# Adafruit_1_54inch_240x240_rev_G.net
KiCad netlist of a schematic drawn in EAGLE
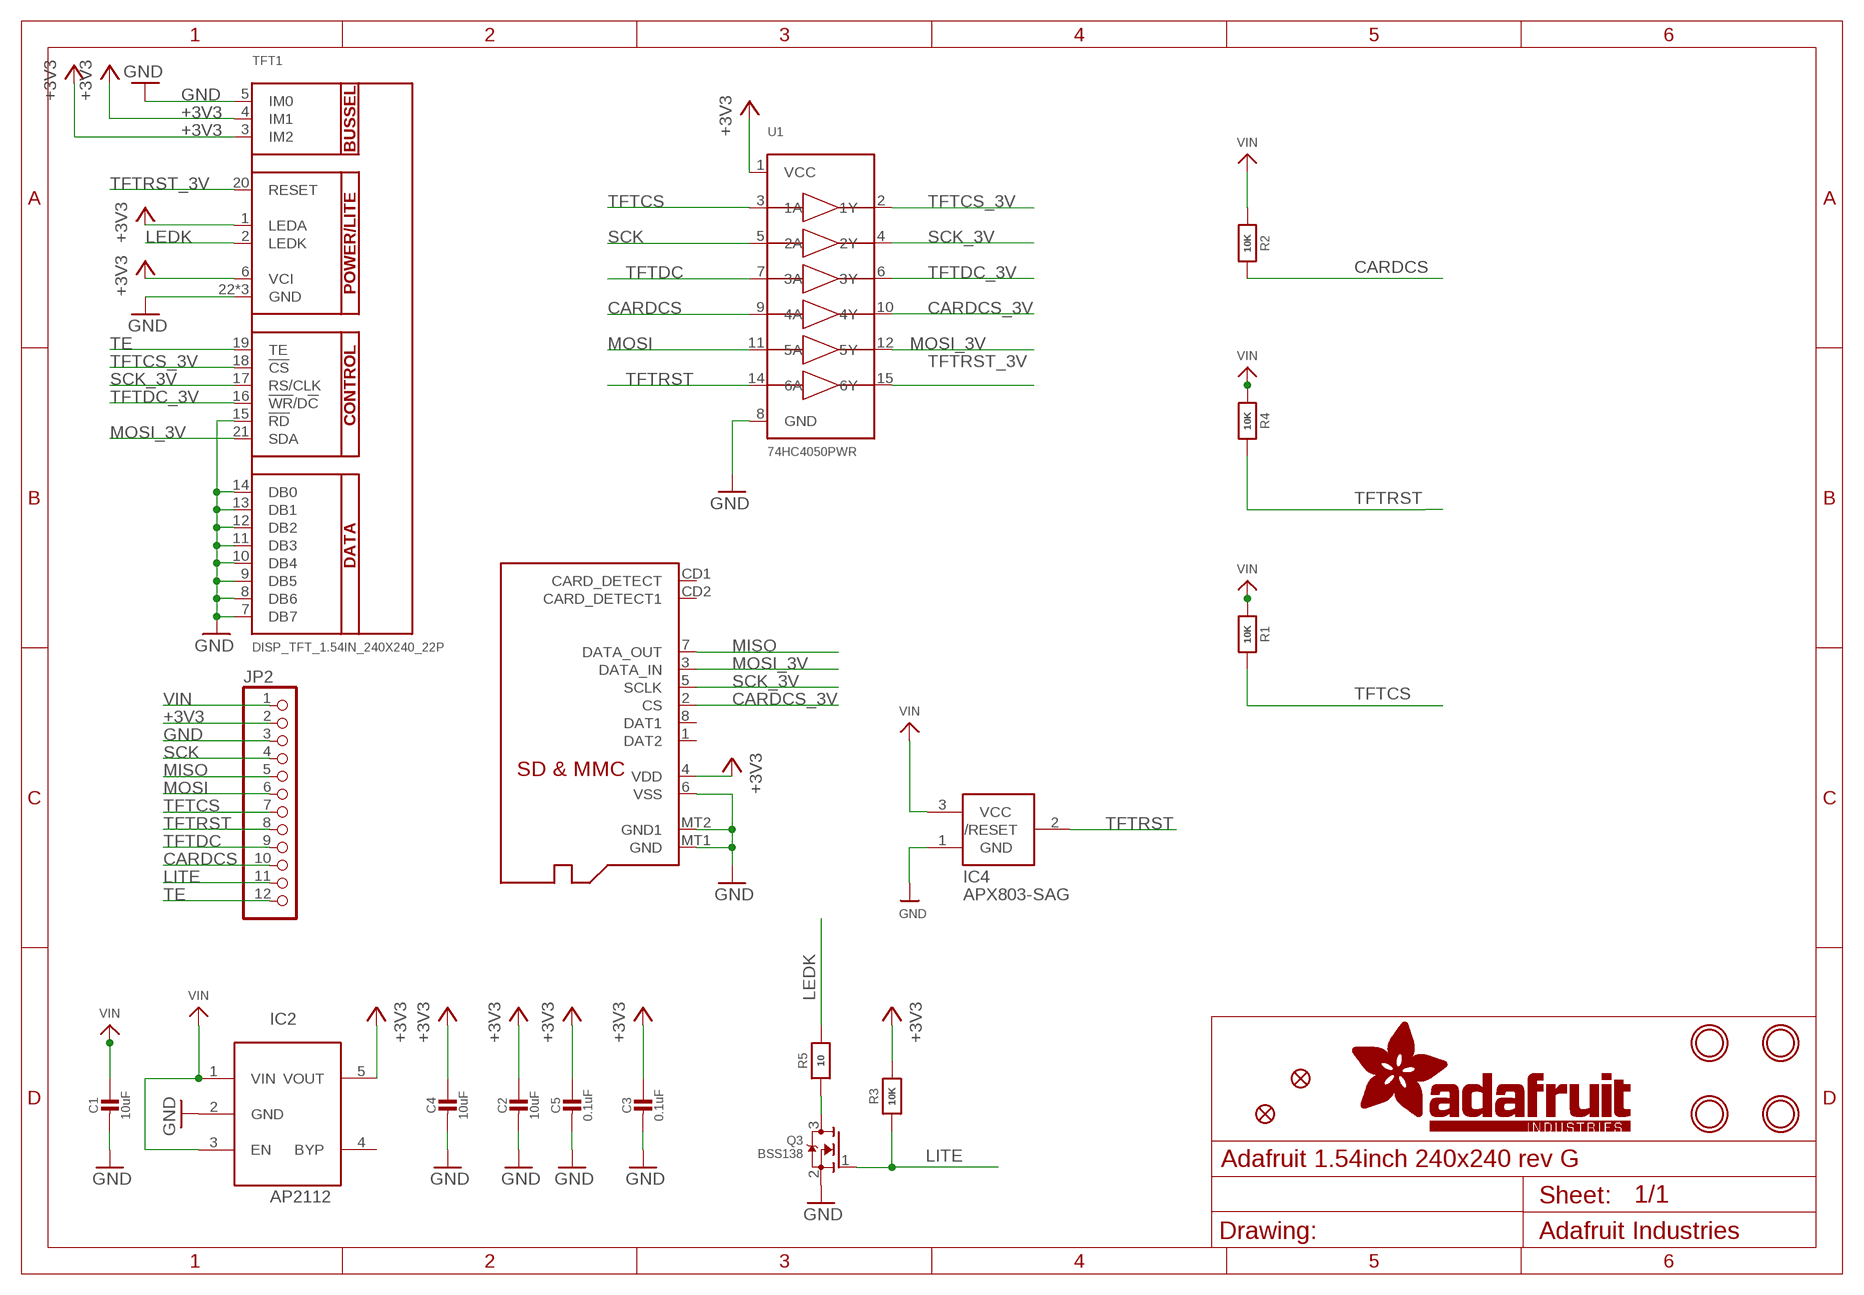
[diagram p0: schematic, sheet 1]

(export (version "E")
  (design (tool "Eeschema 10.0.6"))
  (components
    (comp (ref "C1")
      (value "10uF")
      (footprint "eagle-import:0805-NO")
      (libsource (lib "eagle-import") (part "CAP_CERAMIC0805-NOOUTLINE"))
    )
    (comp (ref "C2")
      (value "10uF")
      (footprint "eagle-import:0805-NO")
      (libsource (lib "eagle-import") (part "CAP_CERAMIC0805-NOOUTLINE"))
    )
    (comp (ref "C3")
      (value "0.1uF")
      (footprint "eagle-import:0603-NO")
      (libsource (lib "eagle-import") (part "CAP_CERAMIC0603_NO"))
    )
    (comp (ref "C4")
      (value "10uF")
      (footprint "eagle-import:0805-NO")
      (libsource (lib "eagle-import") (part "CAP_CERAMIC0805-NOOUTLINE"))
    )
    (comp (ref "C5")
      (value "0.1uF")
      (footprint "eagle-import:0603-NO")
      (libsource (lib "eagle-import") (part "CAP_CERAMIC0603_NO"))
    )
    (comp (ref "IC2")
      (value "AP2112")
      (footprint "eagle-import:SOT23-5L")
      (libsource (lib "eagle-import") (part "LP298XS"))
    )
    (comp (ref "IC4")
      (value "APX803-SAG")
      (footprint "eagle-import:SOT23")
      (libsource (lib "eagle-import") (part "AXP083-SAG"))
    )
    (comp (ref "JP2")
      (value "HEADER-1X1276MIL")
      (footprint "eagle-import:1X12_ROUND_76MIL")
      (libsource (lib "eagle-import") (part "HEADER-1X1276MIL"))
    )
    (comp (ref "Q2")
      (value "MICROSD")
      (footprint "eagle-import:MICROSD")
      (libsource (lib "eagle-import") (part "MICROSD"))
    )
    (comp (ref "Q3")
      (value "BSS138")
      (footprint "eagle-import:SOT23-WIDE")
      (libsource (lib "eagle-import") (part "MOSFET-NWIDE"))
    )
    (comp (ref "R1")
      (value "10K")
      (footprint "eagle-import:0603-NO")
      (libsource (lib "eagle-import") (part "RESISTOR_0603_NOOUT"))
    )
    (comp (ref "R2")
      (value "10K")
      (footprint "eagle-import:0603-NO")
      (libsource (lib "eagle-import") (part "RESISTOR_0603_NOOUT"))
    )
    (comp (ref "R3")
      (value "10K")
      (footprint "eagle-import:0603-NO")
      (libsource (lib "eagle-import") (part "RESISTOR_0603_NOOUT"))
    )
    (comp (ref "R4")
      (value "10K")
      (footprint "eagle-import:0603-NO")
      (libsource (lib "eagle-import") (part "RESISTOR_0603_NOOUT"))
    )
    (comp (ref "R5")
      (value "10")
      (footprint "eagle-import:0603-NO")
      (libsource (lib "eagle-import") (part "RESISTOR_0603_NOOUT"))
    )
    (comp (ref "TFT1")
      (value "DISP_TFT_1.54IN_240X240_22P")
      (footprint "eagle-import:TFT_1.54IN_240X240_22PIN")
      (libsource (lib "eagle-import") (part "DISP_TFT_1.54IN_240X240_22P"))
    )
    (comp (ref "U$4")
      (value "FIDUCIAL_1MM")
      (footprint "eagle-import:FIDUCIAL_1MM")
      (libsource (lib "eagle-import") (part "FIDUCIAL_1MM"))
    )
    (comp (ref "U$5")
      (value "FIDUCIAL_1MM")
      (footprint "eagle-import:FIDUCIAL_1MM")
      (libsource (lib "eagle-import") (part "FIDUCIAL_1MM"))
    )
    (comp (ref "U$7")
      (value "MOUNTINGHOLE2.5")
      (footprint "eagle-import:MOUNTINGHOLE_2.5_PLATED")
      (libsource (lib "eagle-import") (part "MOUNTINGHOLE2.5"))
    )
    (comp (ref "U$8")
      (value "MOUNTINGHOLE2.5")
      (footprint "eagle-import:MOUNTINGHOLE_2.5_PLATED")
      (libsource (lib "eagle-import") (part "MOUNTINGHOLE2.5"))
    )
    (comp (ref "U$9")
      (value "MOUNTINGHOLE2.5")
      (footprint "eagle-import:MOUNTINGHOLE_2.5_PLATED")
      (libsource (lib "eagle-import") (part "MOUNTINGHOLE2.5"))
    )
    (comp (ref "U$10")
      (value "MOUNTINGHOLE2.5")
      (footprint "eagle-import:MOUNTINGHOLE_2.5_PLATED")
      (libsource (lib "eagle-import") (part "MOUNTINGHOLE2.5"))
    )
    (comp (ref "U1")
      (value "74HC4050PWR")
      (footprint "eagle-import:TSSOP16")
      (libsource (lib "eagle-import") (part "74HC4050DTSSOP"))
    )
  )
  (nets
    (net (code "1") (name "+3V3") (class "Default")
      (node (ref "C2") (pin "1") (pinfunction "1_1") (pintype "passive"))
      (node (ref "C3") (pin "1") (pinfunction "1_1") (pintype "passive"))
      (node (ref "C4") (pin "1") (pinfunction "1_1") (pintype "passive"))
      (node (ref "C5") (pin "1") (pinfunction "1_1") (pintype "passive"))
      (node (ref "IC2") (pin "5") (pinfunction "VOUT_5") (pintype "bidirectional"))
      (node (ref "JP2") (pin "2") (pinfunction "2_2") (pintype "passive"))
      (node (ref "Q2") (pin "4") (pinfunction "VDD_4") (pintype "power_in"))
      (node (ref "R3") (pin "2") (pinfunction "2_2") (pintype "passive"))
      (node (ref "TFT1") (pin "1") (pinfunction "LEDA_1") (pintype "input"))
      (node (ref "TFT1") (pin "3") (pinfunction "IM2_3") (pintype "input"))
      (node (ref "TFT1") (pin "4") (pinfunction "IM1_4") (pintype "input"))
      (node (ref "TFT1") (pin "6") (pinfunction "VCI_6") (pintype "power_in"))
      (node (ref "U1") (pin "1") (pinfunction "VCC_1") (pintype "bidirectional"))
    )
    (net (code "2") (name "/CARDCS") (class "Default")
      (node (ref "JP2") (pin "10") (pinfunction "10_10") (pintype "passive"))
      (node (ref "R2") (pin "1") (pinfunction "1_1") (pintype "passive"))
      (node (ref "U1") (pin "9") (pinfunction "4A_9") (pintype "bidirectional"))
    )
    (net (code "3") (name "/CARDCS_3V") (class "Default")
      (node (ref "Q2") (pin "2") (pinfunction "CS_2") (pintype "input"))
      (node (ref "U1") (pin "10") (pinfunction "4Y_10") (pintype "bidirectional"))
    )
    (net (code "4") (name "/LEDK") (class "Default")
      (node (ref "R5") (pin "2") (pinfunction "2_2") (pintype "passive"))
      (node (ref "TFT1") (pin "2") (pinfunction "LEDK_2") (pintype "input"))
    )
    (net (code "5") (name "/LITE") (class "Default")
      (node (ref "JP2") (pin "11") (pinfunction "11_11") (pintype "passive"))
      (node (ref "Q3") (pin "1") (pinfunction "G_1") (pintype "bidirectional"))
      (node (ref "R3") (pin "1") (pinfunction "1_1") (pintype "passive"))
    )
    (net (code "6") (name "/MISO") (class "Default")
      (node (ref "JP2") (pin "5") (pinfunction "5_5") (pintype "passive"))
      (node (ref "Q2") (pin "7") (pinfunction "DATA_OUT_7") (pintype "output"))
    )
    (net (code "7") (name "/MOSI") (class "Default")
      (node (ref "JP2") (pin "6") (pinfunction "6_6") (pintype "passive"))
      (node (ref "U1") (pin "11") (pinfunction "5A_11") (pintype "bidirectional"))
    )
    (net (code "8") (name "/MOSI_3V") (class "Default")
      (node (ref "Q2") (pin "3") (pinfunction "DATA_IN_3") (pintype "input"))
      (node (ref "TFT1") (pin "21") (pinfunction "SDA_21") (pintype "bidirectional"))
      (node (ref "U1") (pin "12") (pinfunction "5Y_12") (pintype "bidirectional"))
    )
    (net (code "9") (name "/SCK") (class "Default")
      (node (ref "JP2") (pin "4") (pinfunction "4_4") (pintype "passive"))
      (node (ref "U1") (pin "5") (pinfunction "2A_5") (pintype "bidirectional"))
    )
    (net (code "10") (name "/SCK_3V") (class "Default")
      (node (ref "Q2") (pin "5") (pinfunction "SCLK_5") (pintype "input"))
      (node (ref "TFT1") (pin "17") (pinfunction "RS/CLK_17") (pintype "input"))
      (node (ref "U1") (pin "4") (pinfunction "2Y_4") (pintype "bidirectional"))
    )
    (net (code "11") (name "/TE") (class "Default")
      (node (ref "JP2") (pin "12") (pinfunction "12_12") (pintype "passive"))
      (node (ref "TFT1") (pin "19") (pinfunction "TE_19") (pintype "output"))
    )
    (net (code "12") (name "/TFTCS") (class "Default")
      (node (ref "JP2") (pin "7") (pinfunction "7_7") (pintype "passive"))
      (node (ref "R1") (pin "1") (pinfunction "1_1") (pintype "passive"))
      (node (ref "U1") (pin "3") (pinfunction "1A_3") (pintype "bidirectional"))
    )
    (net (code "13") (name "/TFTCS_3V") (class "Default")
      (node (ref "TFT1") (pin "18") (pinfunction "~{CS}_18") (pintype "input"))
      (node (ref "U1") (pin "2") (pinfunction "1Y_2") (pintype "bidirectional"))
    )
    (net (code "14") (name "/TFTDC") (class "Default")
      (node (ref "JP2") (pin "9") (pinfunction "9_9") (pintype "passive"))
      (node (ref "U1") (pin "7") (pinfunction "3A_7") (pintype "bidirectional"))
    )
    (net (code "15") (name "/TFTDC_3V") (class "Default")
      (node (ref "TFT1") (pin "16") (pinfunction "~{WR}/D~{C}_16") (pintype "input"))
      (node (ref "U1") (pin "6") (pinfunction "3Y_6") (pintype "bidirectional"))
    )
    (net (code "16") (name "/TFTRST") (class "Default")
      (node (ref "IC4") (pin "2") (pinfunction "/RESET_2") (pintype "output"))
      (node (ref "JP2") (pin "8") (pinfunction "8_8") (pintype "passive"))
      (node (ref "R4") (pin "1") (pinfunction "1_1") (pintype "passive"))
      (node (ref "U1") (pin "14") (pinfunction "6A_14") (pintype "bidirectional"))
    )
    (net (code "17") (name "/TFTRST_3V") (class "Default")
      (node (ref "TFT1") (pin "20") (pinfunction "RESET_20") (pintype "input"))
      (node (ref "U1") (pin "15") (pinfunction "6Y_15") (pintype "bidirectional"))
    )
    (net (code "18") (name "GND") (class "Default")
      (node (ref "C1") (pin "2") (pinfunction "2_2") (pintype "passive"))
      (node (ref "C2") (pin "2") (pinfunction "2_2") (pintype "passive"))
      (node (ref "C3") (pin "2") (pinfunction "2_2") (pintype "passive"))
      (node (ref "C4") (pin "2") (pinfunction "2_2") (pintype "passive"))
      (node (ref "C5") (pin "2") (pinfunction "2_2") (pintype "passive"))
      (node (ref "IC2") (pin "2") (pinfunction "GND_2") (pintype "bidirectional"))
      (node (ref "IC4") (pin "1") (pinfunction "GND_1") (pintype "power_in"))
      (node (ref "JP2") (pin "3") (pinfunction "3_3") (pintype "passive"))
      (node (ref "Q2") (pin "6") (pinfunction "VSS_6") (pintype "power_in"))
      (node (ref "Q2") (pin "MT1") (pinfunction "GND_MT1") (pintype "power_in"))
      (node (ref "Q2") (pin "MT2") (pinfunction "GND1_MT2") (pintype "power_in"))
      (node (ref "Q3") (pin "2") (pinfunction "S_2") (pintype "bidirectional"))
      (node (ref "TFT1") (pin "10") (pinfunction "DB4_10") (pintype "bidirectional"))
      (node (ref "TFT1") (pin "11") (pinfunction "DB3_11") (pintype "bidirectional"))
      (node (ref "TFT1") (pin "12") (pinfunction "DB2_12") (pintype "bidirectional"))
      (node (ref "TFT1") (pin "13") (pinfunction "DB1_13") (pintype "bidirectional"))
      (node (ref "TFT1") (pin "14") (pinfunction "DB0_14") (pintype "bidirectional"))
      (node (ref "TFT1") (pin "15") (pinfunction "~{RD}_15") (pintype "input"))
      (node (ref "TFT1") (pin "22") (pinfunction "GND_22") (pintype "power_in"))
      (node (ref "TFT1") (pin "5") (pinfunction "IM0_5") (pintype "input"))
      (node (ref "TFT1") (pin "7") (pinfunction "DB7_7") (pintype "bidirectional"))
      (node (ref "TFT1") (pin "8") (pinfunction "DB6_8") (pintype "bidirectional"))
      (node (ref "TFT1") (pin "9") (pinfunction "DB5_9") (pintype "bidirectional"))
      (node (ref "TFT1") (pin "SUPPORT1") (pinfunction "GND_SUPPORT1") (pintype "power_in"))
      (node (ref "TFT1") (pin "SUPPORT2") (pinfunction "GND_SUPPORT2") (pintype "power_in"))
      (node (ref "U1") (pin "8") (pinfunction "GND_8") (pintype "bidirectional"))
    )
    (net (code "19") (name "Net-(Q3-D)") (class "Default")
      (node (ref "Q3") (pin "3") (pinfunction "D_3") (pintype "bidirectional"))
      (node (ref "R5") (pin "1") (pinfunction "1_1") (pintype "passive"))
    )
    (net (code "20") (name "VIN") (class "Default")
      (node (ref "C1") (pin "1") (pinfunction "1_1") (pintype "passive"))
      (node (ref "IC2") (pin "1") (pinfunction "VIN_1") (pintype "bidirectional"))
      (node (ref "IC2") (pin "3") (pinfunction "EN_3") (pintype "bidirectional"))
      (node (ref "IC4") (pin "3") (pinfunction "VCC_3") (pintype "power_in"))
      (node (ref "JP2") (pin "1") (pinfunction "1_1") (pintype "passive"))
      (node (ref "R1") (pin "2") (pinfunction "2_2") (pintype "passive"))
      (node (ref "R2") (pin "2") (pinfunction "2_2") (pintype "passive"))
      (node (ref "R4") (pin "2") (pinfunction "2_2") (pintype "passive"))
    )
    (net (code "21") (name "unconnected-(IC2-BYP-Pad4)") (class "Default")
      (node (ref "IC2") (pin "4") (pinfunction "BYP_4") (pintype "bidirectional"))
    )
    (net (code "22") (name "unconnected-(Q2-CARD_DETECT-PadCD1)") (class "Default")
      (node (ref "Q2") (pin "CD1") (pinfunction "CARD_DETECT_CD1") (pintype "passive"))
    )
    (net (code "23") (name "unconnected-(Q2-CARD_DETECT1-PadCD2)") (class "Default")
      (node (ref "Q2") (pin "CD2") (pinfunction "CARD_DETECT1_CD2") (pintype "passive"))
    )
    (net (code "24") (name "unconnected-(Q2-DAT1-Pad8)") (class "Default")
      (node (ref "Q2") (pin "8") (pinfunction "DAT1_8") (pintype "bidirectional"))
    )
    (net (code "25") (name "unconnected-(Q2-DAT2-Pad1)") (class "Default")
      (node (ref "Q2") (pin "1") (pinfunction "DAT2_1") (pintype "bidirectional"))
    )
  )
)
